# LED.net
KiCad netlist of a schematic drawn in EAGLE
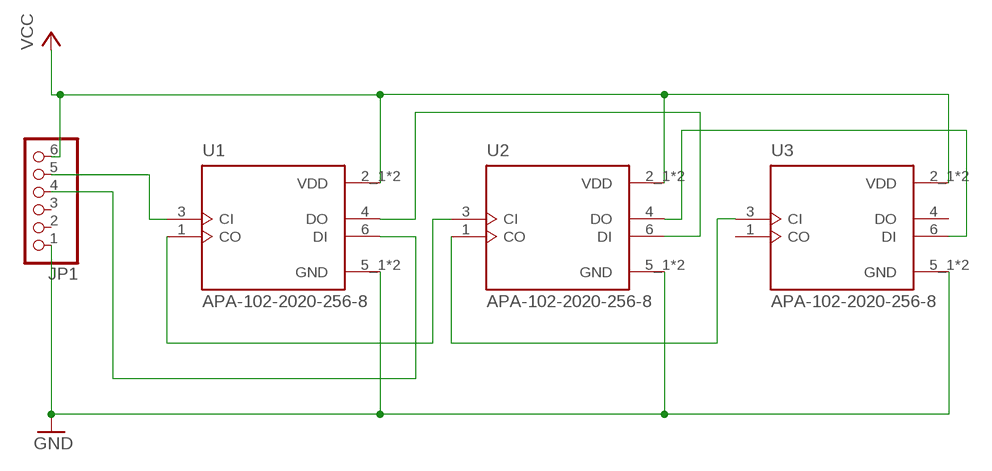
[diagram p0: schematic, sheet 1]

(export (version "E")
  (design (tool "Eeschema 10.0.6"))
  (components
    (comp (ref "JP1")
      (value "PINHD-1X6CLEAN")
      (footprint "eagle-import:1X06-CLEAN")
      (libsource (lib "eagle-import") (part "PINHD-1X6CLEAN"))
    )
    (comp (ref "U1")
      (value "APA-102-2020-256-8")
      (footprint "eagle-import:LED_APA-102-2020-256-8")
      (fields (field (name "MF") "iPixel LED Light Co."))
      (libsource (lib "eagle-import") (part "APA-102-2020-256-8"))
    )
    (comp (ref "U2")
      (value "APA-102-2020-256-8")
      (footprint "eagle-import:LED_APA-102-2020-256-8")
      (fields (field (name "MF") "iPixel LED Light Co."))
      (libsource (lib "eagle-import") (part "APA-102-2020-256-8"))
    )
    (comp (ref "U3")
      (value "APA-102-2020-256-8")
      (footprint "eagle-import:LED_APA-102-2020-256-8")
      (fields (field (name "MF") "iPixel LED Light Co."))
      (libsource (lib "eagle-import") (part "APA-102-2020-256-8"))
    )
  )
  (nets
    (net (code "1") (name "GND") (class "Default")
      (node (ref "JP1") (pin "1") (pinfunction "1_1") (pintype "passive"))
      (node (ref "U1") (pin "5_1") (pinfunction "GND_5_1") (pintype "power_in"))
      (node (ref "U1") (pin "5_2") (pinfunction "GND_5_2") (pintype "power_in"))
      (node (ref "U2") (pin "5_1") (pinfunction "GND_5_1") (pintype "power_in"))
      (node (ref "U2") (pin "5_2") (pinfunction "GND_5_2") (pintype "power_in"))
      (node (ref "U3") (pin "5_1") (pinfunction "GND_5_1") (pintype "power_in"))
      (node (ref "U3") (pin "5_2") (pinfunction "GND_5_2") (pintype "power_in"))
    )
    (net (code "2") (name "Net-(U1-CI)") (class "Default")
      (node (ref "JP1") (pin "5") (pinfunction "5_5") (pintype "passive"))
      (node (ref "U1") (pin "3") (pinfunction "CI_3") (pintype "input"))
    )
    (net (code "3") (name "Net-(U1-CO)") (class "Default")
      (node (ref "U1") (pin "1") (pinfunction "CO_1") (pintype "output"))
      (node (ref "U2") (pin "3") (pinfunction "CI_3") (pintype "input"))
    )
    (net (code "4") (name "Net-(U1-DI)") (class "Default")
      (node (ref "JP1") (pin "4") (pinfunction "4_4") (pintype "passive"))
      (node (ref "U1") (pin "6") (pinfunction "DI_6") (pintype "input"))
    )
    (net (code "5") (name "Net-(U1-DO)") (class "Default")
      (node (ref "U1") (pin "4") (pinfunction "DO_4") (pintype "output"))
      (node (ref "U2") (pin "6") (pinfunction "DI_6") (pintype "input"))
    )
    (net (code "6") (name "Net-(U2-CO)") (class "Default")
      (node (ref "U2") (pin "1") (pinfunction "CO_1") (pintype "output"))
      (node (ref "U3") (pin "3") (pinfunction "CI_3") (pintype "input"))
    )
    (net (code "7") (name "Net-(U2-DO)") (class "Default")
      (node (ref "U2") (pin "4") (pinfunction "DO_4") (pintype "output"))
      (node (ref "U3") (pin "6") (pinfunction "DI_6") (pintype "input"))
    )
    (net (code "8") (name "VCC") (class "Default")
      (node (ref "JP1") (pin "6") (pinfunction "6_6") (pintype "passive"))
      (node (ref "U1") (pin "2_1") (pinfunction "VDD_2_1") (pintype "power_in"))
      (node (ref "U1") (pin "2_2") (pinfunction "VDD_2_2") (pintype "power_in"))
      (node (ref "U2") (pin "2_1") (pinfunction "VDD_2_1") (pintype "power_in"))
      (node (ref "U2") (pin "2_2") (pinfunction "VDD_2_2") (pintype "power_in"))
      (node (ref "U3") (pin "2_1") (pinfunction "VDD_2_1") (pintype "power_in"))
      (node (ref "U3") (pin "2_2") (pinfunction "VDD_2_2") (pintype "power_in"))
    )
    (net (code "9") (name "unconnected-(JP1-Pad2)") (class "Default")
      (node (ref "JP1") (pin "2") (pinfunction "2_2") (pintype "passive"))
    )
    (net (code "10") (name "unconnected-(JP1-Pad3)") (class "Default")
      (node (ref "JP1") (pin "3") (pinfunction "3_3") (pintype "passive"))
    )
    (net (code "11") (name "unconnected-(U3-CO-Pad1)") (class "Default")
      (node (ref "U3") (pin "1") (pinfunction "CO_1") (pintype "output"))
    )
    (net (code "12") (name "unconnected-(U3-DO-Pad4)") (class "Default")
      (node (ref "U3") (pin "4") (pinfunction "DO_4") (pintype "output"))
    )
  )
)
